# TeensyROM.net
KiCad netlist of a schematic drawn in EAGLE
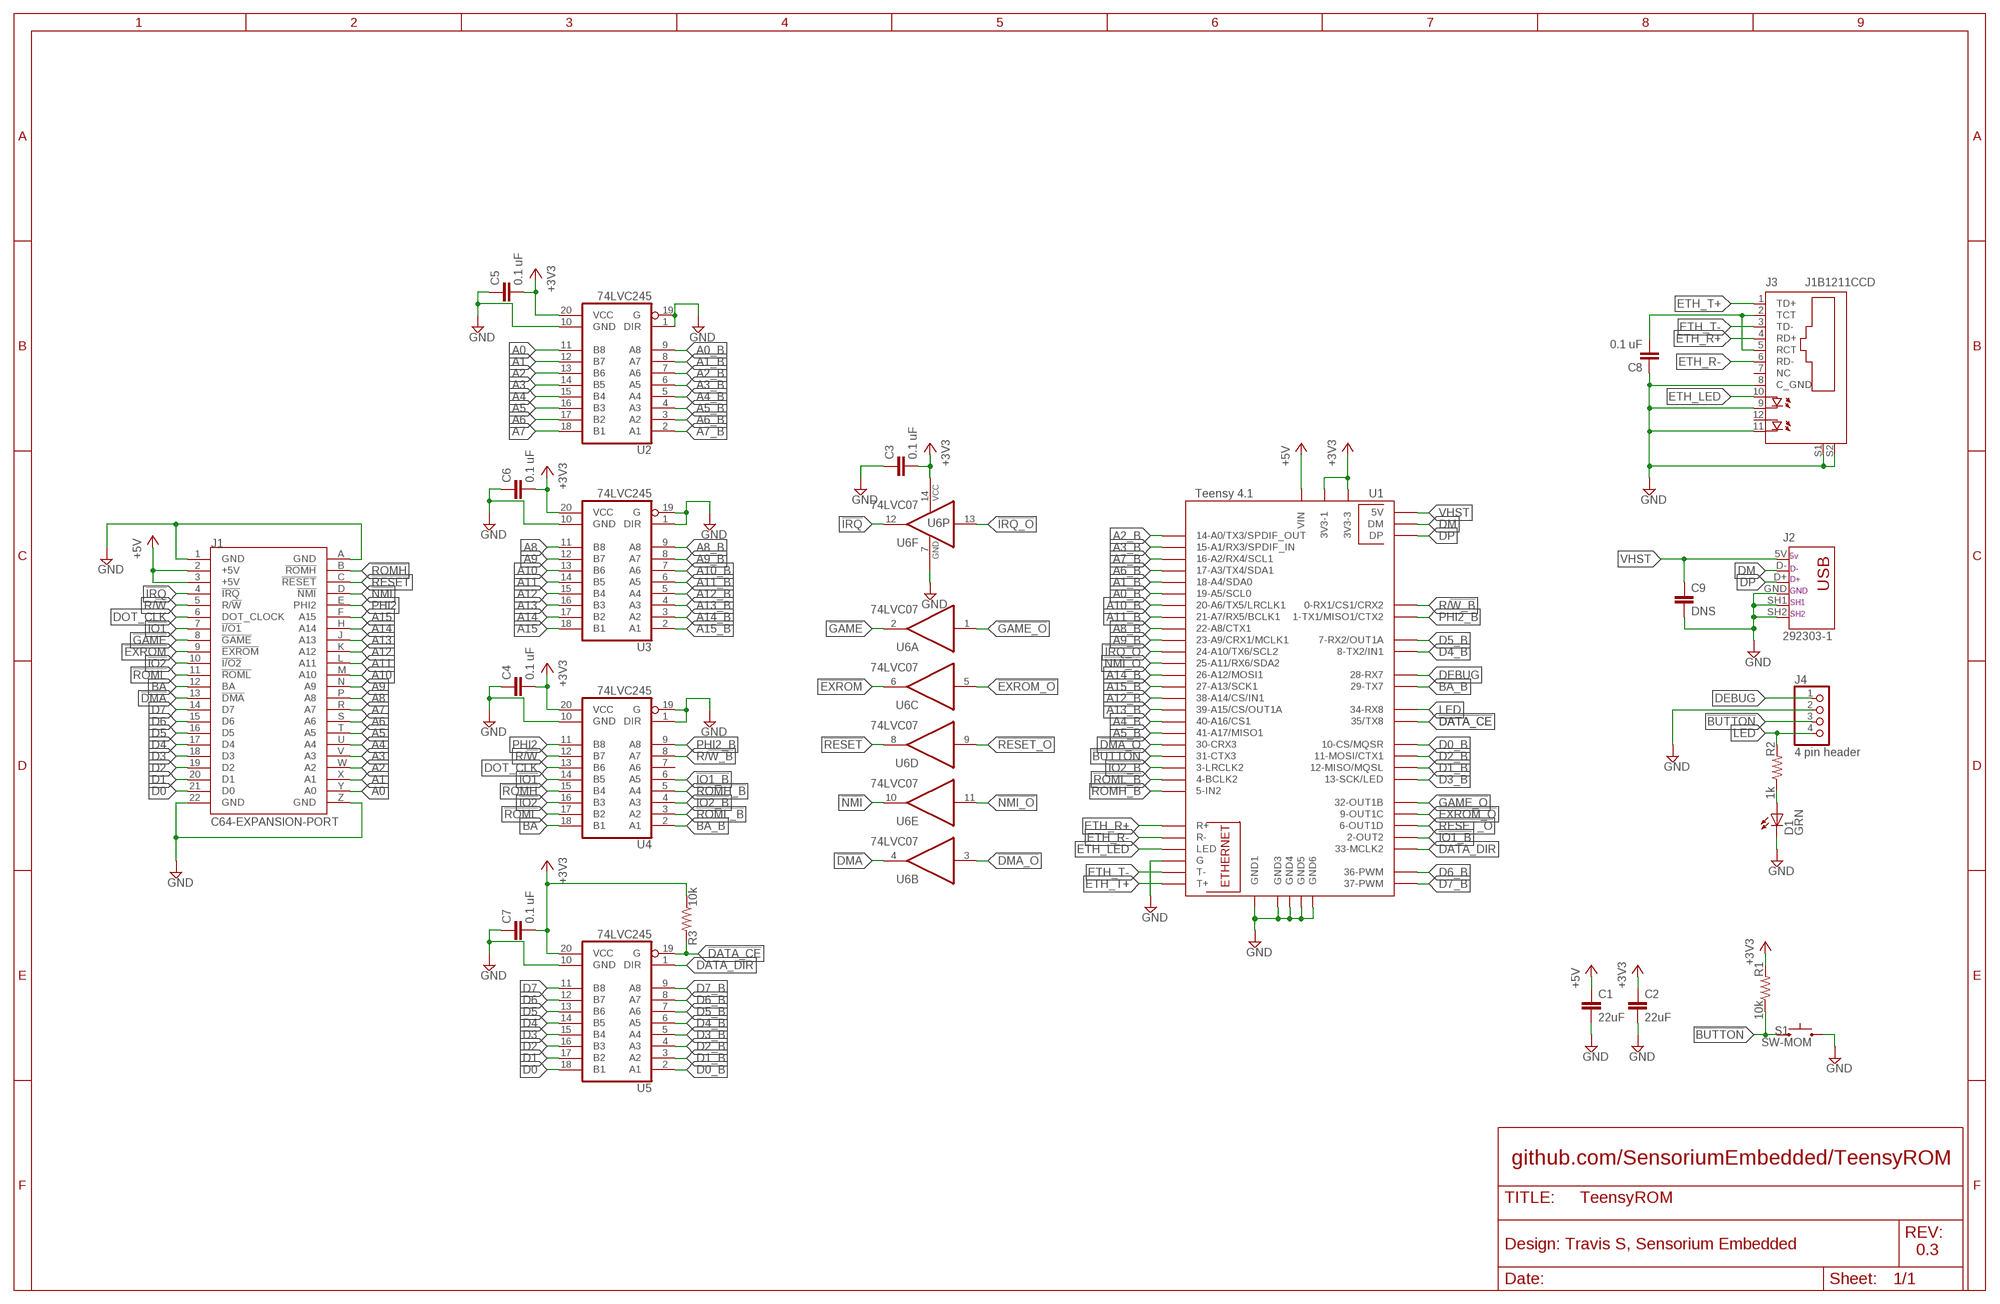
[diagram p0: schematic, sheet 1]

(export (version "E")
  (design (tool "Eeschema 10.0.6"))
  (components
    (comp (ref "C1")
      (value "22uF")
      (footprint "eagle-import:C1210")
      (libsource (lib "eagle-import") (part "C-EUC1210"))
    )
    (comp (ref "C2")
      (value "22uF")
      (footprint "eagle-import:C1210")
      (libsource (lib "eagle-import") (part "C-EUC1210"))
    )
    (comp (ref "C3")
      (value "0.1 uF")
      (footprint "eagle-import:0805")
      (libsource (lib "eagle-import") (part "CAP-0805-0.1UF-50V"))
    )
    (comp (ref "C4")
      (value "0.1 uF")
      (footprint "eagle-import:0805")
      (libsource (lib "eagle-import") (part "CAP-0805-0.1UF-50V"))
    )
    (comp (ref "C5")
      (value "0.1 uF")
      (footprint "eagle-import:0805")
      (libsource (lib "eagle-import") (part "CAP-0805-0.1UF-50V"))
    )
    (comp (ref "C6")
      (value "0.1 uF")
      (footprint "eagle-import:0805")
      (libsource (lib "eagle-import") (part "CAP-0805-0.1UF-50V"))
    )
    (comp (ref "C7")
      (value "0.1 uF")
      (footprint "eagle-import:0805")
      (libsource (lib "eagle-import") (part "CAP-0805-0.1UF-50V"))
    )
    (comp (ref "C8")
      (value "0.1 uF")
      (footprint "eagle-import:0805")
      (libsource (lib "eagle-import") (part "CAP-0805-0.1UF-50V"))
    )
    (comp (ref "C9")
      (value "DNS")
      (footprint "eagle-import:C1210")
      (libsource (lib "eagle-import") (part "C-EUC1210"))
    )
    (comp (ref "D1")
      (value "GRN")
      (footprint "eagle-import:LED-3MM-PTH")
      (libsource (lib "eagle-import") (part "LED-3MM-GRN"))
    )
    (comp (ref "J1")
      (value "C64-EXPANSION-PORT")
      (footprint "eagle-import:EXPANSIO_SQ")
      (libsource (lib "eagle-import") (part "C64-EXPANSIONPNARROW"))
    )
    (comp (ref "J2")
      (value "292303-1")
      (footprint "eagle-import:USB")
      (libsource (lib "eagle-import") (part "USB-787616"))
    )
    (comp (ref "J3")
      (value "J1B1211CCD")
      (footprint "eagle-import:CONN12_J1B1211CCD_WIZ")
      (fields (field (name "COPYRIGHT") "Copyright (C) 2023 Ultra Librarian. All rights reserved."))
      (libsource (lib "eagle-import") (part "J1B1211CCD"))
    )
    (comp (ref "J4")
      (value "4 pin header")
      (footprint "eagle-import:1X04")
      (libsource (lib "eagle-import") (part "PINHD-1X4"))
    )
    (comp (ref "R1")
      (value "10k")
      (footprint "eagle-import:R0805")
      (libsource (lib "eagle-import") (part "R-US_R0805"))
    )
    (comp (ref "R2")
      (value "1k")
      (footprint "eagle-import:R0805")
      (libsource (lib "eagle-import") (part "R-US_R0805"))
    )
    (comp (ref "R3")
      (value "10k")
      (footprint "eagle-import:R0805")
      (libsource (lib "eagle-import") (part "R-US_R0805"))
    )
    (comp (ref "S1")
      (value "SW-MOM")
      (footprint "eagle-import:TACTILE-PTH")
      (libsource (lib "eagle-import") (part "SWITCH-MOMENTARY-2PTH"))
    )
    (comp (ref "U1")
      (value "Teensy 4.1")
      (footprint "eagle-import:TEENSY41")
      (libsource (lib "eagle-import") (part "TEENSY41"))
    )
    (comp (ref "U2")
      (value "74LVC245")
      (footprint "eagle-import:SO20W")
      (libsource (lib "eagle-import") (part "74245DWLS"))
    )
    (comp (ref "U3")
      (value "74LVC245")
      (footprint "eagle-import:SO20W")
      (libsource (lib "eagle-import") (part "74245DWLS"))
    )
    (comp (ref "U4")
      (value "74LVC245")
      (footprint "eagle-import:SO20W")
      (libsource (lib "eagle-import") (part "74245DWLS"))
    )
    (comp (ref "U5")
      (value "74LVC245")
      (footprint "eagle-import:SO20W")
      (libsource (lib "eagle-import") (part "74245DWLS"))
    )
    (comp (ref "U6")
      (value "74LVC07")
      (footprint "eagle-import:SO14")
      (libsource (lib "eagle-import") (part "7407DLS"))
    )
  )
  (nets
    (net (code "1") (name "+3V3") (class "Default")
      (node (ref "C2") (pin "1") (pinfunction "1_1") (pintype "passive"))
      (node (ref "C3") (pin "2") (pinfunction "2_2") (pintype "passive"))
      (node (ref "C4") (pin "2") (pinfunction "2_2") (pintype "passive"))
      (node (ref "C5") (pin "2") (pinfunction "2_2") (pintype "passive"))
      (node (ref "C6") (pin "2") (pinfunction "2_2") (pintype "passive"))
      (node (ref "C7") (pin "2") (pinfunction "2_2") (pintype "passive"))
      (node (ref "R1") (pin "2") (pinfunction "2_2") (pintype "passive"))
      (node (ref "R3") (pin "1") (pinfunction "1_1") (pintype "passive"))
      (node (ref "U1") (pin "3V3-1") (pinfunction "3V3-1_3V3-1") (pintype "bidirectional"))
      (node (ref "U1") (pin "3V3-3") (pinfunction "3V3-3_3V3-3") (pintype "bidirectional"))
      (node (ref "U2") (pin "20") (pinfunction "VCC_20") (pintype "bidirectional"))
      (node (ref "U3") (pin "20") (pinfunction "VCC_20") (pintype "bidirectional"))
      (node (ref "U4") (pin "20") (pinfunction "VCC_20") (pintype "bidirectional"))
      (node (ref "U5") (pin "20") (pinfunction "VCC_20") (pintype "bidirectional"))
      (node (ref "U6") (pin "14") (pinfunction "VCC_14") (pintype "bidirectional"))
    )
    (net (code "2") (name "+5V") (class "Default")
      (node (ref "C1") (pin "1") (pinfunction "1_1") (pintype "passive"))
      (node (ref "J1") (pin "2") (pinfunction "+5V_2") (pintype "power_in"))
      (node (ref "J1") (pin "3") (pinfunction "+5V_3") (pintype "power_in"))
      (node (ref "U1") (pin "VIN") (pinfunction "VIN_VIN") (pintype "bidirectional"))
    )
    (net (code "3") (name "/R{slash}~{W_B}") (class "Default")
      (node (ref "U1") (pin "0-RX1/CS1/CRX2") (pinfunction "0-RX1/CS1/CRX2_0-RX1/CS1/CRX2") (pintype "bidirectional"))
      (node (ref "U4") (pin "8") (pinfunction "A7_8") (pintype "bidirectional"))
    )
    (net (code "4") (name "/R{slash}~{W}") (class "Default")
      (node (ref "J1") (pin "5") (pinfunction "R/~{W}_5") (pintype "output"))
      (node (ref "U4") (pin "12") (pinfunction "B7_12") (pintype "bidirectional"))
    )
    (net (code "5") (name "/~{BUTTON}") (class "Default")
      (node (ref "J4") (pin "3") (pinfunction "3_3") (pintype "passive"))
      (node (ref "R1") (pin "1") (pinfunction "1_1") (pintype "passive"))
      (node (ref "S1") (pin "3") (pinfunction "2_3") (pintype "passive"))
      (node (ref "U1") (pin "31-CTX3") (pinfunction "31-CTX3_31-CTX3") (pintype "bidirectional"))
    )
    (net (code "6") (name "/~{DATA_CE}") (class "Default")
      (node (ref "R3") (pin "2") (pinfunction "2_2") (pintype "passive"))
      (node (ref "U1") (pin "35-TX8") (pinfunction "35/TX8_35-TX8") (pintype "bidirectional"))
      (node (ref "U5") (pin "19") (pinfunction "G_19") (pintype "input"))
    )
    (net (code "7") (name "/~{DMA_O}") (class "Default")
      (node (ref "U1") (pin "30-CRX3") (pinfunction "30-CRX3_30-CRX3") (pintype "bidirectional"))
      (node (ref "U6") (pin "3") (pinfunction "I_3") (pintype "input"))
    )
    (net (code "8") (name "/~{DMA}") (class "Default")
      (node (ref "J1") (pin "13") (pinfunction "~{DMA}_13") (pintype "input"))
      (node (ref "U6") (pin "4") (pinfunction "O_4") (pintype "open_collector"))
    )
    (net (code "9") (name "/~{EXROM_O}") (class "Default")
      (node (ref "U1") (pin "9-OUT1C") (pinfunction "9-OUT1C_9-OUT1C") (pintype "bidirectional"))
      (node (ref "U6") (pin "5") (pinfunction "I_5") (pintype "input"))
    )
    (net (code "10") (name "/~{EXROM}") (class "Default")
      (node (ref "J1") (pin "9") (pinfunction "~{EXROM}_9") (pintype "input"))
      (node (ref "U6") (pin "6") (pinfunction "O_6") (pintype "open_collector"))
    )
    (net (code "11") (name "/~{GAME_O}") (class "Default")
      (node (ref "U1") (pin "32-OUT1B") (pinfunction "32-OUT1B_32-OUT1B") (pintype "bidirectional"))
      (node (ref "U6") (pin "1") (pinfunction "I_1") (pintype "input"))
    )
    (net (code "12") (name "/~{GAME}") (class "Default")
      (node (ref "J1") (pin "8") (pinfunction "~{GAME}_8") (pintype "input"))
      (node (ref "U6") (pin "2") (pinfunction "O_2") (pintype "open_collector"))
    )
    (net (code "13") (name "/~{IO1_B}") (class "Default")
      (node (ref "U1") (pin "2-OUT2") (pinfunction "2-OUT2_2-OUT2") (pintype "bidirectional"))
      (node (ref "U4") (pin "6") (pinfunction "A5_6") (pintype "bidirectional"))
    )
    (net (code "14") (name "/~{IO1}") (class "Default")
      (node (ref "J1") (pin "7") (pinfunction "~{I/O1}_7") (pintype "output"))
      (node (ref "U4") (pin "14") (pinfunction "B5_14") (pintype "bidirectional"))
    )
    (net (code "15") (name "/~{IO2_B}") (class "Default")
      (node (ref "U1") (pin "3-LRCLK2") (pinfunction "3-LRCLK2_3-LRCLK2") (pintype "bidirectional"))
      (node (ref "U4") (pin "4") (pinfunction "A3_4") (pintype "bidirectional"))
    )
    (net (code "16") (name "/~{IO2}") (class "Default")
      (node (ref "J1") (pin "10") (pinfunction "~{I/O2}_10") (pintype "output"))
      (node (ref "U4") (pin "16") (pinfunction "B3_16") (pintype "bidirectional"))
    )
    (net (code "17") (name "/~{IRQ_O}") (class "Default")
      (node (ref "U1") (pin "24-A10/TX6/SCL2") (pinfunction "24-A10/TX6/SCL2_24-A10/TX6/SCL2") (pintype "bidirectional"))
      (node (ref "U6") (pin "13") (pinfunction "I_13") (pintype "input"))
    )
    (net (code "18") (name "/~{IRQ}") (class "Default")
      (node (ref "J1") (pin "4") (pinfunction "~{IRQ}_4") (pintype "input"))
      (node (ref "U6") (pin "12") (pinfunction "O_12") (pintype "open_collector"))
    )
    (net (code "19") (name "/~{NMI_O}") (class "Default")
      (node (ref "U1") (pin "25-A11/RX6/SDA2") (pinfunction "25-A11/RX6/SDA2_25-A11/RX6/SDA2") (pintype "bidirectional"))
      (node (ref "U6") (pin "11") (pinfunction "I_11") (pintype "input"))
    )
    (net (code "20") (name "/~{NMI}") (class "Default")
      (node (ref "J1") (pin "D") (pinfunction "~{NMI}_D") (pintype "input"))
      (node (ref "U6") (pin "10") (pinfunction "O_10") (pintype "open_collector"))
    )
    (net (code "21") (name "/~{RESET_O}") (class "Default")
      (node (ref "U1") (pin "6-OUT1D") (pinfunction "6-OUT1D_6-OUT1D") (pintype "bidirectional"))
      (node (ref "U6") (pin "9") (pinfunction "I_9") (pintype "input"))
    )
    (net (code "22") (name "/~{RESET}") (class "Default")
      (node (ref "J1") (pin "C") (pinfunction "~{RESET}_C") (pintype "open_collector"))
      (node (ref "U6") (pin "8") (pinfunction "O_8") (pintype "open_collector"))
    )
    (net (code "23") (name "/~{ROMH_B}") (class "Default")
      (node (ref "U1") (pin "5-IN2") (pinfunction "5-IN2_5-IN2") (pintype "bidirectional"))
      (node (ref "U4") (pin "5") (pinfunction "A4_5") (pintype "bidirectional"))
    )
    (net (code "24") (name "/~{ROMH}") (class "Default")
      (node (ref "J1") (pin "B") (pinfunction "~{ROMH}_B") (pintype "output"))
      (node (ref "U4") (pin "15") (pinfunction "B4_15") (pintype "bidirectional"))
    )
    (net (code "25") (name "/~{ROML_B}") (class "Default")
      (node (ref "U1") (pin "4-BCLK2") (pinfunction "4-BCLK2_4-BCLK2") (pintype "bidirectional"))
      (node (ref "U4") (pin "3") (pinfunction "A2_3") (pintype "bidirectional"))
    )
    (net (code "26") (name "/~{ROML}") (class "Default")
      (node (ref "J1") (pin "11") (pinfunction "~{ROML}_11") (pintype "output"))
      (node (ref "U4") (pin "17") (pinfunction "B2_17") (pintype "bidirectional"))
    )
    (net (code "27") (name "A0") (class "Default")
      (node (ref "J1") (pin "Y") (pinfunction "A0_Y") (pintype "bidirectional"))
      (node (ref "U2") (pin "11") (pinfunction "B8_11") (pintype "bidirectional"))
    )
    (net (code "28") (name "A0_B") (class "Default")
      (node (ref "U1") (pin "19-A5/SCL0") (pinfunction "19-A5/SCL0_19-A5/SCL0") (pintype "bidirectional"))
      (node (ref "U2") (pin "9") (pinfunction "A8_9") (pintype "bidirectional"))
    )
    (net (code "29") (name "A1") (class "Default")
      (node (ref "J1") (pin "X") (pinfunction "A1_X") (pintype "bidirectional"))
      (node (ref "U2") (pin "12") (pinfunction "B7_12") (pintype "bidirectional"))
    )
    (net (code "30") (name "A1_B") (class "Default")
      (node (ref "U1") (pin "18-A4/SDA0") (pinfunction "18-A4/SDA0_18-A4/SDA0") (pintype "bidirectional"))
      (node (ref "U2") (pin "8") (pinfunction "A7_8") (pintype "bidirectional"))
    )
    (net (code "31") (name "A2") (class "Default")
      (node (ref "J1") (pin "W") (pinfunction "A2_W") (pintype "bidirectional"))
      (node (ref "U2") (pin "13") (pinfunction "B6_13") (pintype "bidirectional"))
    )
    (net (code "32") (name "A2_B") (class "Default")
      (node (ref "U1") (pin "14-A0/TX3/SPDIF_OUT") (pinfunction "14-A0/TX3/SPDIF_OUT_14-A0/TX3/SPDIF_OUT") (pintype "bidirectional"))
      (node (ref "U2") (pin "7") (pinfunction "A6_7") (pintype "bidirectional"))
    )
    (net (code "33") (name "A3") (class "Default")
      (node (ref "J1") (pin "V") (pinfunction "A3_V") (pintype "bidirectional"))
      (node (ref "U2") (pin "14") (pinfunction "B5_14") (pintype "bidirectional"))
    )
    (net (code "34") (name "A3_B") (class "Default")
      (node (ref "U1") (pin "15-A1/RX3/SPDIF_IN") (pinfunction "15-A1/RX3/SPDIF_IN_15-A1/RX3/SPDIF_IN") (pintype "bidirectional"))
      (node (ref "U2") (pin "6") (pinfunction "A5_6") (pintype "bidirectional"))
    )
    (net (code "35") (name "A4") (class "Default")
      (node (ref "J1") (pin "U") (pinfunction "A4_U") (pintype "bidirectional"))
      (node (ref "U2") (pin "15") (pinfunction "B4_15") (pintype "bidirectional"))
    )
    (net (code "36") (name "A4_B") (class "Default")
      (node (ref "U1") (pin "40-A16/CS1") (pinfunction "40-A16/CS1_40-A16/CS1") (pintype "bidirectional"))
      (node (ref "U2") (pin "5") (pinfunction "A4_5") (pintype "bidirectional"))
    )
    (net (code "37") (name "A5") (class "Default")
      (node (ref "J1") (pin "T") (pinfunction "A5_T") (pintype "bidirectional"))
      (node (ref "U2") (pin "16") (pinfunction "B3_16") (pintype "bidirectional"))
    )
    (net (code "38") (name "A5_B") (class "Default")
      (node (ref "U1") (pin "41-A17/MISO1") (pinfunction "41-A17/MISO1_41-A17/MISO1") (pintype "bidirectional"))
      (node (ref "U2") (pin "4") (pinfunction "A3_4") (pintype "bidirectional"))
    )
    (net (code "39") (name "A6") (class "Default")
      (node (ref "J1") (pin "S") (pinfunction "A6_S") (pintype "bidirectional"))
      (node (ref "U2") (pin "17") (pinfunction "B2_17") (pintype "bidirectional"))
    )
    (net (code "40") (name "A6_B") (class "Default")
      (node (ref "U1") (pin "17-A3/TX4/SDA1") (pinfunction "17-A3/TX4/SDA1_17-A3/TX4/SDA1") (pintype "bidirectional"))
      (node (ref "U2") (pin "3") (pinfunction "A2_3") (pintype "bidirectional"))
    )
    (net (code "41") (name "A7") (class "Default")
      (node (ref "J1") (pin "R") (pinfunction "A7_R") (pintype "bidirectional"))
      (node (ref "U2") (pin "18") (pinfunction "B1_18") (pintype "bidirectional"))
    )
    (net (code "42") (name "A7_B") (class "Default")
      (node (ref "U1") (pin "16-A2/RX4/SCL1") (pinfunction "16-A2/RX4/SCL1_16-A2/RX4/SCL1") (pintype "bidirectional"))
      (node (ref "U2") (pin "2") (pinfunction "A1_2") (pintype "bidirectional"))
    )
    (net (code "43") (name "A8") (class "Default")
      (node (ref "J1") (pin "P") (pinfunction "A8_P") (pintype "bidirectional"))
      (node (ref "U3") (pin "11") (pinfunction "B8_11") (pintype "bidirectional"))
    )
    (net (code "44") (name "A8_B") (class "Default")
      (node (ref "U1") (pin "22-A8/CTX1") (pinfunction "22-A8/CTX1_22-A8/CTX1") (pintype "bidirectional"))
      (node (ref "U3") (pin "9") (pinfunction "A8_9") (pintype "bidirectional"))
    )
    (net (code "45") (name "A9") (class "Default")
      (node (ref "J1") (pin "N") (pinfunction "A9_N") (pintype "bidirectional"))
      (node (ref "U3") (pin "12") (pinfunction "B7_12") (pintype "bidirectional"))
    )
    (net (code "46") (name "A9_B") (class "Default")
      (node (ref "U1") (pin "23-A9/CRX1/MCLK1") (pinfunction "23-A9/CRX1/MCLK1_23-A9/CRX1/MCLK1") (pintype "bidirectional"))
      (node (ref "U3") (pin "8") (pinfunction "A7_8") (pintype "bidirectional"))
    )
    (net (code "47") (name "A10") (class "Default")
      (node (ref "J1") (pin "M") (pinfunction "A10_M") (pintype "bidirectional"))
      (node (ref "U3") (pin "13") (pinfunction "B6_13") (pintype "bidirectional"))
    )
    (net (code "48") (name "A10_B") (class "Default")
      (node (ref "U1") (pin "20-A6/TX5/LRCLK1") (pinfunction "20-A6/TX5/LRCLK1_20-A6/TX5/LRCLK1") (pintype "bidirectional"))
      (node (ref "U3") (pin "7") (pinfunction "A6_7") (pintype "bidirectional"))
    )
    (net (code "49") (name "A11") (class "Default")
      (node (ref "J1") (pin "L") (pinfunction "A11_L") (pintype "bidirectional"))
      (node (ref "U3") (pin "14") (pinfunction "B5_14") (pintype "bidirectional"))
    )
    (net (code "50") (name "A11_B") (class "Default")
      (node (ref "U1") (pin "21-A7/RX5/BCLK1") (pinfunction "21-A7/RX5/BCLK1_21-A7/RX5/BCLK1") (pintype "bidirectional"))
      (node (ref "U3") (pin "6") (pinfunction "A5_6") (pintype "bidirectional"))
    )
    (net (code "51") (name "A12") (class "Default")
      (node (ref "J1") (pin "K") (pinfunction "A12_K") (pintype "bidirectional"))
      (node (ref "U3") (pin "15") (pinfunction "B4_15") (pintype "bidirectional"))
    )
    (net (code "52") (name "A12_B") (class "Default")
      (node (ref "U1") (pin "38-A14/CS/IN1") (pinfunction "38-A14/CS/IN1_38-A14/CS/IN1") (pintype "bidirectional"))
      (node (ref "U3") (pin "5") (pinfunction "A4_5") (pintype "bidirectional"))
    )
    (net (code "53") (name "A13") (class "Default")
      (node (ref "J1") (pin "J") (pinfunction "A13_J") (pintype "bidirectional"))
      (node (ref "U3") (pin "16") (pinfunction "B3_16") (pintype "bidirectional"))
    )
    (net (code "54") (name "A13_B") (class "Default")
      (node (ref "U1") (pin "39-A15/CS/OUT1A") (pinfunction "39-A15/CS/OUT1A_39-A15/CS/OUT1A") (pintype "bidirectional"))
      (node (ref "U3") (pin "4") (pinfunction "A3_4") (pintype "bidirectional"))
    )
    (net (code "55") (name "A14") (class "Default")
      (node (ref "J1") (pin "H") (pinfunction "A14_H") (pintype "bidirectional"))
      (node (ref "U3") (pin "17") (pinfunction "B2_17") (pintype "bidirectional"))
    )
    (net (code "56") (name "A14_B") (class "Default")
      (node (ref "U1") (pin "26-A12/MOSI1") (pinfunction "26-A12/MOSI1_26-A12/MOSI1") (pintype "bidirectional"))
      (node (ref "U3") (pin "3") (pinfunction "A2_3") (pintype "bidirectional"))
    )
    (net (code "57") (name "A15") (class "Default")
      (node (ref "J1") (pin "F") (pinfunction "A15_F") (pintype "bidirectional"))
      (node (ref "U3") (pin "18") (pinfunction "B1_18") (pintype "bidirectional"))
    )
    (net (code "58") (name "A15_B") (class "Default")
      (node (ref "U1") (pin "27-A13/SCK1") (pinfunction "27-A13/SCK1_27-A13/SCK1") (pintype "bidirectional"))
      (node (ref "U3") (pin "2") (pinfunction "A1_2") (pintype "bidirectional"))
    )
    (net (code "59") (name "BA") (class "Default")
      (node (ref "J1") (pin "12") (pinfunction "BA_12") (pintype "output"))
      (node (ref "U4") (pin "18") (pinfunction "B1_18") (pintype "bidirectional"))
    )
    (net (code "60") (name "BA_B") (class "Default")
      (node (ref "U1") (pin "29-TX7") (pinfunction "29-TX7_29-TX7") (pintype "bidirectional"))
      (node (ref "U4") (pin "2") (pinfunction "A1_2") (pintype "bidirectional"))
    )
    (net (code "61") (name "D0") (class "Default")
      (node (ref "J1") (pin "21") (pinfunction "D0_21") (pintype "bidirectional"))
      (node (ref "U5") (pin "18") (pinfunction "B1_18") (pintype "bidirectional"))
    )
    (net (code "62") (name "D0_B") (class "Default")
      (node (ref "U1") (pin "10-CS\\MQSR") (pinfunction "10-CS/MQSR_10-CS\\MQSR") (pintype "bidirectional"))
      (node (ref "U5") (pin "2") (pinfunction "A1_2") (pintype "bidirectional"))
    )
    (net (code "63") (name "D1") (class "Default")
      (node (ref "J1") (pin "20") (pinfunction "D1_20") (pintype "bidirectional"))
      (node (ref "U5") (pin "17") (pinfunction "B2_17") (pintype "bidirectional"))
    )
    (net (code "64") (name "D1_B") (class "Default")
      (node (ref "U1") (pin "12-MISO/MQSL") (pinfunction "12-MISO/MQSL_12-MISO/MQSL") (pintype "bidirectional"))
      (node (ref "U5") (pin "3") (pinfunction "A2_3") (pintype "bidirectional"))
    )
    (net (code "65") (name "D2") (class "Default")
      (node (ref "J1") (pin "19") (pinfunction "D2_19") (pintype "bidirectional"))
      (node (ref "U5") (pin "16") (pinfunction "B3_16") (pintype "bidirectional"))
    )
    (net (code "66") (name "D2_B") (class "Default")
      (node (ref "U1") (pin "11-MOSI/CTX1") (pinfunction "11-MOSI/CTX1_11-MOSI/CTX1") (pintype "bidirectional"))
      (node (ref "U5") (pin "4") (pinfunction "A3_4") (pintype "bidirectional"))
    )
    (net (code "67") (name "D3") (class "Default")
      (node (ref "J1") (pin "18") (pinfunction "D3_18") (pintype "bidirectional"))
      (node (ref "U5") (pin "15") (pinfunction "B4_15") (pintype "bidirectional"))
    )
    (net (code "68") (name "D3_B") (class "Default")
      (node (ref "U1") (pin "13-SCK/LED") (pinfunction "13-SCK/LED_13-SCK/LED") (pintype "bidirectional"))
      (node (ref "U5") (pin "5") (pinfunction "A4_5") (pintype "bidirectional"))
    )
    (net (code "69") (name "D4") (class "Default")
      (node (ref "J1") (pin "17") (pinfunction "D4_17") (pintype "bidirectional"))
      (node (ref "U5") (pin "14") (pinfunction "B5_14") (pintype "bidirectional"))
    )
    (net (code "70") (name "D4_B") (class "Default")
      (node (ref "U1") (pin "8-TX2/IN1") (pinfunction "8-TX2/IN1_8-TX2/IN1") (pintype "bidirectional"))
      (node (ref "U5") (pin "6") (pinfunction "A5_6") (pintype "bidirectional"))
    )
    (net (code "71") (name "D5") (class "Default")
      (node (ref "J1") (pin "16") (pinfunction "D5_16") (pintype "bidirectional"))
      (node (ref "U5") (pin "13") (pinfunction "B6_13") (pintype "bidirectional"))
    )
    (net (code "72") (name "D5_B") (class "Default")
      (node (ref "U1") (pin "7-RX2/OUT1A") (pinfunction "7-RX2/OUT1A_7-RX2/OUT1A") (pintype "bidirectional"))
      (node (ref "U5") (pin "7") (pinfunction "A6_7") (pintype "bidirectional"))
    )
    (net (code "73") (name "D6") (class "Default")
      (node (ref "J1") (pin "15") (pinfunction "D6_15") (pintype "bidirectional"))
      (node (ref "U5") (pin "12") (pinfunction "B7_12") (pintype "bidirectional"))
    )
    (net (code "74") (name "D6_B") (class "Default")
      (node (ref "U1") (pin "36-PWM") (pinfunction "36-PWM_36-PWM") (pintype "bidirectional"))
      (node (ref "U5") (pin "8") (pinfunction "A7_8") (pintype "bidirectional"))
    )
    (net (code "75") (name "D7") (class "Default")
      (node (ref "J1") (pin "14") (pinfunction "D7_14") (pintype "bidirectional"))
      (node (ref "U5") (pin "11") (pinfunction "B8_11") (pintype "bidirectional"))
    )
    (net (code "76") (name "D7_B") (class "Default")
      (node (ref "U1") (pin "37-PWM") (pinfunction "37-PWM_37-PWM") (pintype "bidirectional"))
      (node (ref "U5") (pin "9") (pinfunction "A8_9") (pintype "bidirectional"))
    )
    (net (code "77") (name "DATA_DIR") (class "Default")
      (node (ref "U1") (pin "33-MCLK2") (pinfunction "33-MCLK2_33-MCLK2") (pintype "bidirectional"))
      (node (ref "U5") (pin "1") (pinfunction "DIR_1") (pintype "input"))
    )
    (net (code "78") (name "DEBUG") (class "Default")
      (node (ref "J4") (pin "1") (pinfunction "1_1") (pintype "passive"))
      (node (ref "U1") (pin "28-RX7") (pinfunction "28-RX7_28-RX7") (pintype "bidirectional"))
    )
    (net (code "79") (name "DM") (class "Default")
      (node (ref "J2") (pin "D-") (pinfunction "2_D-") (pintype "passive"))
      (node (ref "U1") (pin "DM") (pinfunction "DM_DM") (pintype "bidirectional"))
    )
    (net (code "80") (name "DOT_CLK") (class "Default")
      (node (ref "J1") (pin "6") (pinfunction "DOT_CLOCK_6") (pintype "output"))
      (node (ref "U4") (pin "13") (pinfunction "B6_13") (pintype "bidirectional"))
    )
    (net (code "81") (name "DP") (class "Default")
      (node (ref "J2") (pin "D+") (pinfunction "3_D+") (pintype "passive"))
      (node (ref "U1") (pin "DP") (pinfunction "DP_DP") (pintype "bidirectional"))
    )
    (net (code "82") (name "ETH_LED") (class "Default")
      (node (ref "J3") (pin "10") (pinfunction "A_10") (pintype "passive"))
      (node (ref "U1") (pin "LED") (pinfunction "LED_LED") (pintype "bidirectional"))
    )
    (net (code "83") (name "ETH_R+") (class "Default")
      (node (ref "J3") (pin "4") (pinfunction "RD+_4") (pintype "passive"))
      (node (ref "U1") (pin "R+") (pinfunction "R+_R+") (pintype "bidirectional"))
    )
    (net (code "84") (name "ETH_R-") (class "Default")
      (node (ref "J3") (pin "6") (pinfunction "RD-_6") (pintype "passive"))
      (node (ref "U1") (pin "R-") (pinfunction "R-_R-") (pintype "bidirectional"))
    )
    (net (code "85") (name "ETH_T+") (class "Default")
      (node (ref "J3") (pin "1") (pinfunction "TD+_1") (pintype "passive"))
      (node (ref "U1") (pin "T+") (pinfunction "T+_T+") (pintype "bidirectional"))
    )
    (net (code "86") (name "ETH_T-") (class "Default")
      (node (ref "J3") (pin "3") (pinfunction "TD-_3") (pintype "passive"))
      (node (ref "U1") (pin "T-") (pinfunction "T-_T-") (pintype "bidirectional"))
    )
    (net (code "87") (name "GND") (class "Default")
      (node (ref "C1") (pin "2") (pinfunction "2_2") (pintype "passive"))
      (node (ref "C2") (pin "2") (pinfunction "2_2") (pintype "passive"))
      (node (ref "C3") (pin "1") (pinfunction "1_1") (pintype "passive"))
      (node (ref "C4") (pin "1") (pinfunction "1_1") (pintype "passive"))
      (node (ref "C5") (pin "1") (pinfunction "1_1") (pintype "passive"))
      (node (ref "C6") (pin "1") (pinfunction "1_1") (pintype "passive"))
      (node (ref "C7") (pin "1") (pinfunction "1_1") (pintype "passive"))
      (node (ref "C8") (pin "1") (pinfunction "1_1") (pintype "passive"))
      (node (ref "C9") (pin "2") (pinfunction "2_2") (pintype "passive"))
      (node (ref "D1") (pin "K") (pinfunction "C_K") (pintype "passive"))
      (node (ref "J1") (pin "1") (pinfunction "GND_1") (pintype "power_in"))
      (node (ref "J1") (pin "22") (pinfunction "GND_22") (pintype "power_in"))
      (node (ref "J1") (pin "A") (pinfunction "GND_A") (pintype "power_in"))
      (node (ref "J1") (pin "Z") (pinfunction "GND_Z") (pintype "power_in"))
      (node (ref "J2") (pin "GND") (pinfunction "4_GND") (pintype "passive"))
      (node (ref "J2") (pin "SH1") (pinfunction "5_SH1") (pintype "passive"))
      (node (ref "J2") (pin "SH2") (pinfunction "6_SH2") (pintype "passive"))
      (node (ref "J3") (pin "11") (pinfunction "C1_11") (pintype "passive"))
      (node (ref "J3") (pin "8") (pinfunction "C_GND_8") (pintype "passive"))
      (node (ref "J3") (pin "9") (pinfunction "C_9") (pintype "passive"))
      (node (ref "J3") (pin "S1") (pinfunction "S1_S1") (pintype "passive"))
      (node (ref "J3") (pin "S2") (pinfunction "S2_S2") (pintype "passive"))
      (node (ref "J4") (pin "2") (pinfunction "2_2") (pintype "passive"))
      (node (ref "S1") (pin "1") (pinfunction "1_1") (pintype "passive"))
      (node (ref "U1") (pin "G") (pinfunction "G_G") (pintype "bidirectional"))
      (node (ref "U1") (pin "GND1") (pinfunction "GND1_GND1") (pintype "bidirectional"))
      (node (ref "U1") (pin "GND3") (pinfunction "GND3_GND3") (pintype "bidirectional"))
      (node (ref "U1") (pin "GND4") (pinfunction "GND4_GND4") (pintype "bidirectional"))
      (node (ref "U1") (pin "GND5") (pinfunction "GND5_GND5") (pintype "bidirectional"))
      (node (ref "U1") (pin "GND6") (pinfunction "GND6_GND6") (pintype "bidirectional"))
      (node (ref "U2") (pin "1") (pinfunction "DIR_1") (pintype "input"))
      (node (ref "U2") (pin "10") (pinfunction "GND_10") (pintype "bidirectional"))
      (node (ref "U2") (pin "19") (pinfunction "G_19") (pintype "input"))
      (node (ref "U3") (pin "1") (pinfunction "DIR_1") (pintype "input"))
      (node (ref "U3") (pin "10") (pinfunction "GND_10") (pintype "bidirectional"))
      (node (ref "U3") (pin "19") (pinfunction "G_19") (pintype "input"))
      (node (ref "U4") (pin "1") (pinfunction "DIR_1") (pintype "input"))
      (node (ref "U4") (pin "10") (pinfunction "GND_10") (pintype "bidirectional"))
      (node (ref "U4") (pin "19") (pinfunction "G_19") (pintype "input"))
      (node (ref "U5") (pin "10") (pinfunction "GND_10") (pintype "bidirectional"))
      (node (ref "U6") (pin "7") (pinfunction "GND_7") (pintype "power_in"))
    )
    (net (code "88") (name "LED") (class "Default")
      (node (ref "J4") (pin "4") (pinfunction "4_4") (pintype "passive"))
      (node (ref "R2") (pin "2") (pinfunction "2_2") (pintype "passive"))
      (node (ref "U1") (pin "34-RX8") (pinfunction "34-RX8_34-RX8") (pintype "bidirectional"))
    )
    (net (code "89") (name "Net-(D1-PadA)") (class "Default")
      (node (ref "D1") (pin "A") (pinfunction "A_A") (pintype "passive"))
      (node (ref "R2") (pin "1") (pinfunction "1_1") (pintype "passive"))
    )
    (net (code "90") (name "Net-(J3-RCT)") (class "Default")
      (node (ref "C8") (pin "2") (pinfunction "2_2") (pintype "passive"))
      (node (ref "J3") (pin "2") (pinfunction "TCT_2") (pintype "passive"))
      (node (ref "J3") (pin "5") (pinfunction "RCT_5") (pintype "passive"))
    )
    (net (code "91") (name "PHI2") (class "Default")
      (node (ref "J1") (pin "E") (pinfunction "PHI2_E") (pintype "output"))
      (node (ref "U4") (pin "11") (pinfunction "B8_11") (pintype "bidirectional"))
    )
    (net (code "92") (name "PHI2_B") (class "Default")
      (node (ref "U1") (pin "1-TX1/MISO1/CTX2") (pinfunction "1-TX1/MISO1/CTX2_1-TX1/MISO1/CTX2") (pintype "bidirectional"))
      (node (ref "U4") (pin "9") (pinfunction "A8_9") (pintype "bidirectional"))
    )
    (net (code "93") (name "VHST") (class "Default")
      (node (ref "C9") (pin "1") (pinfunction "1_1") (pintype "passive"))
      (node (ref "J2") (pin "5V") (pinfunction "1_5V") (pintype "passive"))
      (node (ref "U1") (pin "+5V") (pinfunction "5V_+5V") (pintype "bidirectional"))
    )
    (net (code "94") (name "unconnected-(J3-A1-Pad12)") (class "Default")
      (node (ref "J3") (pin "12") (pinfunction "A1_12") (pintype "passive"))
    )
    (net (code "95") (name "unconnected-(J3-NC-Pad7)") (class "Default")
      (node (ref "J3") (pin "7") (pinfunction "NC_7") (pintype "passive"))
    )
    (net (code "96") (name "unconnected-(U4-A6-Pad7)") (class "Default")
      (node (ref "U4") (pin "7") (pinfunction "A6_7") (pintype "bidirectional"))
    )
  )
)
